# 05_Motor.net
KiCad netlist of a schematic drawn in Altium Designer
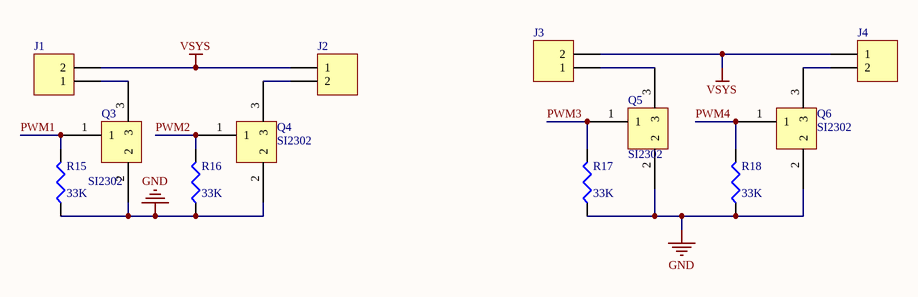
[diagram p0: 05_Motor.SchDoc]

(export (version "E")
  (design (tool "Eeschema 10.0.6"))
  (components
    (comp (ref "J1")
      (value "Header 2")
      (footprint "HDR1X2")
      (description "Header, 2-Pin")
      (fields (field (name "PUBLISHER") "Altium Limited"))
      (libsource (lib "") (part "Header 2_1"))
    )
    (comp (ref "J2")
      (value "Header 2")
      (footprint "HDR1X2")
      (description "Header, 2-Pin")
      (fields (field (name "PUBLISHER") "Altium Limited"))
      (libsource (lib "Miscellaneous Connectors") (part "Header 2"))
    )
    (comp (ref "J3")
      (value "Header 2")
      (footprint "HDR1X2")
      (description "Header, 2-Pin")
      (fields (field (name "PUBLISHER") "Altium Limited"))
      (libsource (lib "") (part "Header 2_1"))
    )
    (comp (ref "J4")
      (value "Header 2")
      (footprint "HDR1X2")
      (description "Header, 2-Pin")
      (fields (field (name "PUBLISHER") "Altium Limited"))
      (libsource (lib "Miscellaneous Connectors") (part "Header 2"))
    )
    (comp (ref "Q3")
      (value "SI2302")
      (footprint "SOT-23_M")
      (libsource (lib "aircraftschlib") (part "SI2302"))
    )
    (comp (ref "Q4")
      (value "SI2302")
      (footprint "SOT-23_M")
      (libsource (lib "aircraftschlib") (part "SI2302"))
    )
    (comp (ref "Q5")
      (value "SI2302")
      (footprint "SOT-23_M")
      (libsource (lib "aircraftschlib") (part "SI2302"))
    )
    (comp (ref "Q6")
      (value "SI2302")
      (footprint "SOT-23_M")
      (libsource (lib "aircraftschlib") (part "SI2302"))
    )
    (comp (ref "R15")
      (value "33K")
      (footprint "0402")
      (description "Resistor")
      (fields (field (name "Comment") "Res3") (field (name "PUBLISHER") "Altium Limited"))
      (libsource (lib "Miscellaneous Devices") (part "Res3"))
    )
    (comp (ref "R16")
      (value "33K")
      (footprint "0402")
      (description "Resistor")
      (fields (field (name "Comment") "Res3") (field (name "PUBLISHER") "Altium Limited"))
      (libsource (lib "Miscellaneous Devices") (part "Res3"))
    )
    (comp (ref "R17")
      (value "33K")
      (footprint "0402")
      (description "Resistor")
      (fields (field (name "Comment") "Res3") (field (name "PUBLISHER") "Altium Limited"))
      (libsource (lib "Miscellaneous Devices") (part "Res3"))
    )
    (comp (ref "R18")
      (value "33K")
      (footprint "0402")
      (description "Resistor")
      (fields (field (name "Comment") "Res3") (field (name "PUBLISHER") "Altium Limited"))
      (libsource (lib "Miscellaneous Devices") (part "Res3"))
    )
  )
  (nets
    (net (code "1") (name "/PWM1") (class "Default")
      (node (ref "Q3") (pin "1") (pinfunction "1_1") (pintype "passive"))
      (node (ref "R15") (pin "2") (pinfunction "2_2") (pintype "passive"))
    )
    (net (code "2") (name "/PWM2") (class "Default")
      (node (ref "Q4") (pin "1") (pinfunction "1_1") (pintype "passive"))
      (node (ref "R16") (pin "2") (pinfunction "2_2") (pintype "passive"))
    )
    (net (code "3") (name "/PWM3") (class "Default")
      (node (ref "Q5") (pin "1") (pinfunction "1_1") (pintype "passive"))
      (node (ref "R17") (pin "2") (pinfunction "2_2") (pintype "passive"))
    )
    (net (code "4") (name "/PWM4") (class "Default")
      (node (ref "Q6") (pin "1") (pinfunction "1_1") (pintype "passive"))
      (node (ref "R18") (pin "2") (pinfunction "2_2") (pintype "passive"))
    )
    (net (code "5") (name "GND") (class "Default")
      (node (ref "Q3") (pin "2") (pinfunction "2_2") (pintype "passive"))
      (node (ref "Q4") (pin "2") (pinfunction "2_2") (pintype "passive"))
      (node (ref "Q5") (pin "2") (pinfunction "2_2") (pintype "passive"))
      (node (ref "Q6") (pin "2") (pinfunction "2_2") (pintype "passive"))
      (node (ref "R15") (pin "1") (pinfunction "1_1") (pintype "passive"))
      (node (ref "R16") (pin "1") (pinfunction "1_1") (pintype "passive"))
      (node (ref "R17") (pin "1") (pinfunction "1_1") (pintype "passive"))
      (node (ref "R18") (pin "1") (pinfunction "1_1") (pintype "passive"))
    )
    (net (code "6") (name "Net-(J1-Pad1)") (class "Default")
      (node (ref "J1") (pin "1") (pinfunction "1_1") (pintype "passive"))
      (node (ref "Q3") (pin "3") (pinfunction "3_3") (pintype "passive"))
    )
    (net (code "7") (name "Net-(J2-Pad2)") (class "Default")
      (node (ref "J2") (pin "2") (pinfunction "2_2") (pintype "passive"))
      (node (ref "Q4") (pin "3") (pinfunction "3_3") (pintype "passive"))
    )
    (net (code "8") (name "Net-(J3-Pad1)") (class "Default")
      (node (ref "J3") (pin "1") (pinfunction "1_1") (pintype "passive"))
      (node (ref "Q5") (pin "3") (pinfunction "3_3") (pintype "passive"))
    )
    (net (code "9") (name "Net-(J4-Pad2)") (class "Default")
      (node (ref "J4") (pin "2") (pinfunction "2_2") (pintype "passive"))
      (node (ref "Q6") (pin "3") (pinfunction "3_3") (pintype "passive"))
    )
    (net (code "10") (name "VSYS") (class "Default")
      (node (ref "J1") (pin "2") (pinfunction "2_2") (pintype "passive"))
      (node (ref "J2") (pin "1") (pinfunction "1_1") (pintype "passive"))
      (node (ref "J3") (pin "2") (pinfunction "2_2") (pintype "passive"))
      (node (ref "J4") (pin "1") (pinfunction "1_1") (pintype "passive"))
    )
  )
)
